# Holder_Accu_Simetric.net
KiCad netlist of a schematic drawn in Altium Designer
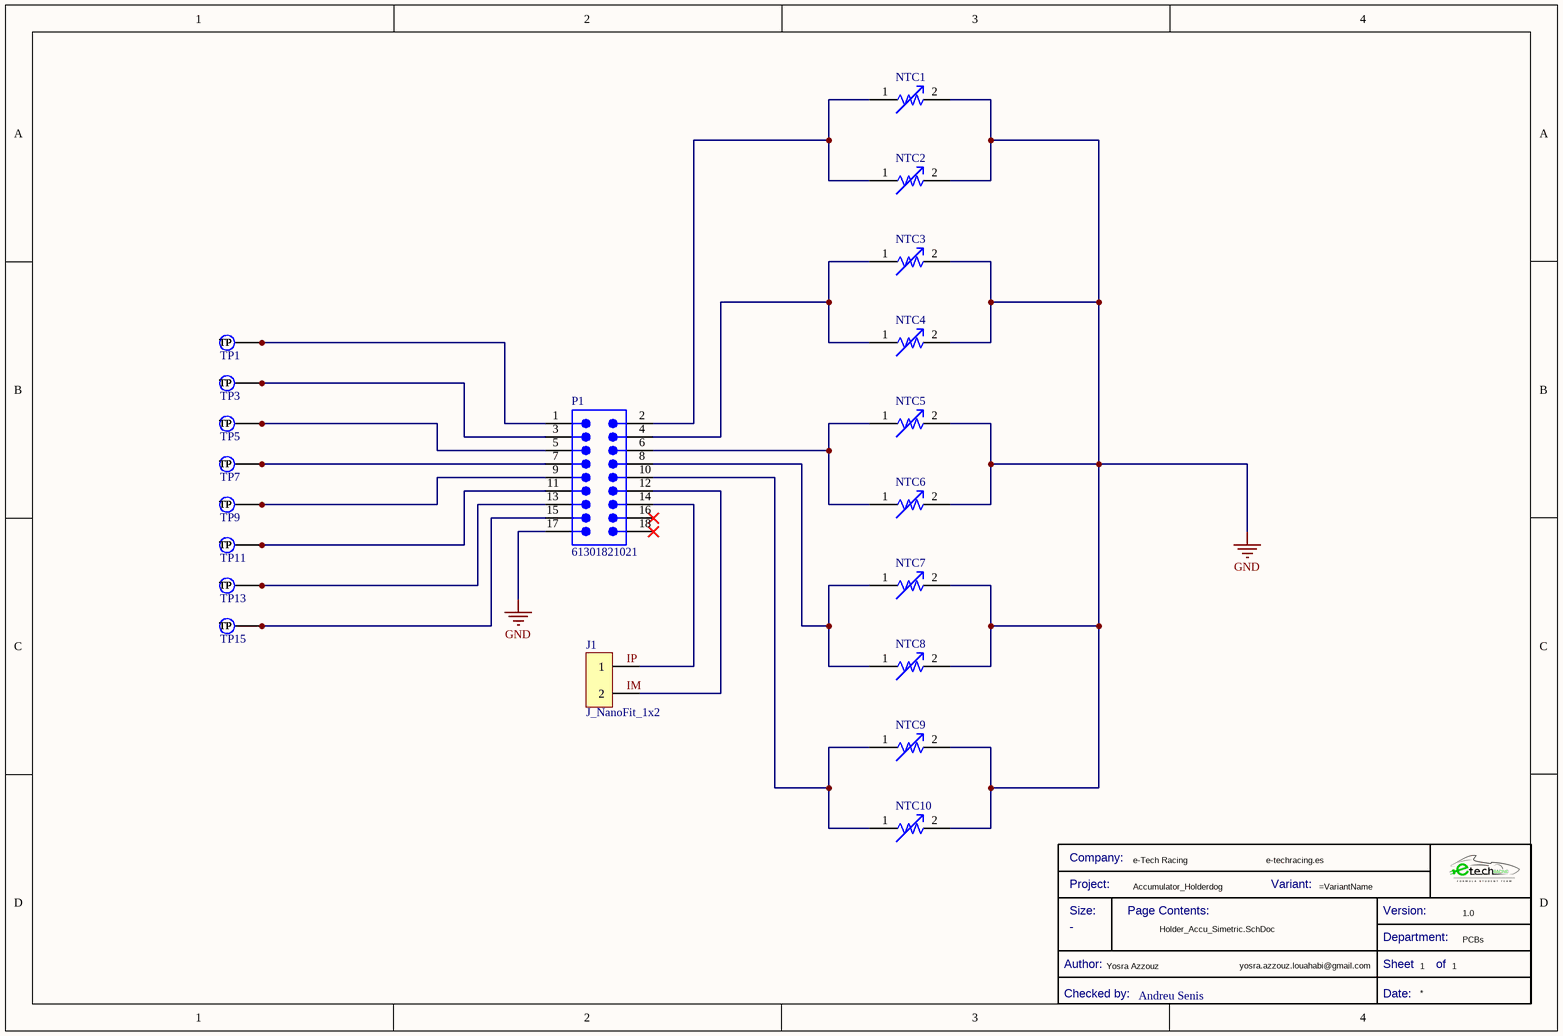
[diagram p0: Holder_Accu_Simetric.SchDoc]

(export (version "E")
  (design (tool "Eeschema 10.0.6"))
  (components
    (comp (ref "*")
      (value "Title Block_template")
      (description "Standard Title Block")
      (fields
        (field (name "SIZE") "-")
        (field (name ".CREATOR") "GP")
        (field (name ".PCBCHECK") "GP")
        (field (name ".SCHCHECK") "GP")
      )
      (libsource (lib "e-Tech_Racing") (part "Title Block_template"))
    )
    (comp (ref "J1")
      (value "J_NanoFit_1x2")
      (footprint "FP-105309-1102-MFG")
      (description "Conn HDR 2 POS 2.5mm Solder ST Thru-Hole 2 Terminal 1 Port Nano-Fit Tray")
      (libsource (lib "EMEA- E-Tech Racing- I'Escola d'Enginyeria de Barcelona Est") (part "Molex Nano-Fit"))
    )
    (comp (ref "NTC1")
      (value "NTC SMD 0805")
      (footprint "RESC2012X10N")
      (description "NTC 0805 package 10kR")
      (libsource (lib "EMEA- E-Tech Racing- I'Escola d'Enginyeria de Barcelona Est") (part "0805"))
    )
    (comp (ref "NTC2")
      (value "NTC SMD 0805")
      (footprint "RESC2012X10N")
      (description "NTC 0805 package 10kR")
      (libsource (lib "EMEA- E-Tech Racing- I'Escola d'Enginyeria de Barcelona Est") (part "0805"))
    )
    (comp (ref "NTC3")
      (value "NTC SMD 0805")
      (footprint "RESC2012X10N")
      (description "NTC 0805 package 10kR")
      (libsource (lib "EMEA- E-Tech Racing- I'Escola d'Enginyeria de Barcelona Est") (part "0805"))
    )
    (comp (ref "NTC4")
      (value "NTC SMD 0805")
      (footprint "RESC2012X10N")
      (description "NTC 0805 package 10kR")
      (libsource (lib "EMEA- E-Tech Racing- I'Escola d'Enginyeria de Barcelona Est") (part "0805"))
    )
    (comp (ref "NTC5")
      (value "NTC SMD 0805")
      (footprint "RESC2012X10N")
      (description "NTC 0805 package 10kR")
      (libsource (lib "EMEA- E-Tech Racing- I'Escola d'Enginyeria de Barcelona Est") (part "0805"))
    )
    (comp (ref "NTC6")
      (value "NTC SMD 0805")
      (footprint "RESC2012X10N")
      (description "NTC 0805 package 10kR")
      (libsource (lib "EMEA- E-Tech Racing- I'Escola d'Enginyeria de Barcelona Est") (part "0805"))
    )
    (comp (ref "NTC7")
      (value "NTC SMD 0805")
      (footprint "RESC2012X10N")
      (description "NTC 0805 package 10kR")
      (libsource (lib "EMEA- E-Tech Racing- I'Escola d'Enginyeria de Barcelona Est") (part "0805"))
    )
    (comp (ref "NTC8")
      (value "NTC SMD 0805")
      (footprint "RESC2012X10N")
      (description "NTC 0805 package 10kR")
      (libsource (lib "EMEA- E-Tech Racing- I'Escola d'Enginyeria de Barcelona Est") (part "0805"))
    )
    (comp (ref "NTC9")
      (value "NTC SMD 0805")
      (footprint "RESC2012X10N")
      (description "NTC 0805 package 10kR")
      (libsource (lib "EMEA- E-Tech Racing- I'Escola d'Enginyeria de Barcelona Est") (part "0805"))
    )
    (comp (ref "NTC10")
      (value "NTC SMD 0805")
      (footprint "RESC2012X10N")
      (description "NTC 0805 package 10kR")
      (libsource (lib "EMEA- E-Tech Racing- I'Escola d'Enginyeria de Barcelona Est") (part "0805"))
    )
    (comp (ref "P1")
      (value "61301821021")
      (footprint "61301821021")
      (libsource (lib "EMEA- E-Tech Racing- I'Escola d'Enginyeria de Barcelona Est") (part "Header_Male_2R_18P"))
    )
    (comp (ref "TP1")
      (value "Test Point")
      (footprint "TESTPOINT_WIDE")
      (description "TestPoint 5x5mm")
      (libsource (lib "e-Tech_Racing") (part "TestPoint_Wide"))
    )
    (comp (ref "TP3")
      (value "Test Point")
      (footprint "TESTPOINT_WIDE")
      (description "TestPoint 5x5mm")
      (libsource (lib "e-Tech_Racing") (part "TestPoint_Wide"))
    )
    (comp (ref "TP5")
      (value "Test Point")
      (footprint "TESTPOINT_WIDE")
      (description "TestPoint 5x5mm")
      (libsource (lib "e-Tech_Racing") (part "TestPoint_Wide"))
    )
    (comp (ref "TP7")
      (value "Test Point")
      (footprint "TESTPOINT_WIDE")
      (description "TestPoint 5x5mm")
      (libsource (lib "e-Tech_Racing") (part "TestPoint_Wide"))
    )
    (comp (ref "TP9")
      (value "Test Point")
      (footprint "TESTPOINT_WIDE")
      (description "TestPoint 5x5mm")
      (libsource (lib "e-Tech_Racing") (part "TestPoint_Wide"))
    )
    (comp (ref "TP11")
      (value "Test Point")
      (footprint "TESTPOINT_WIDE")
      (description "TestPoint 5x5mm")
      (libsource (lib "e-Tech_Racing") (part "TestPoint_Wide"))
    )
    (comp (ref "TP13")
      (value "Test Point")
      (footprint "TESTPOINT_WIDE")
      (description "TestPoint 5x5mm")
      (libsource (lib "e-Tech_Racing") (part "TestPoint_Wide"))
    )
    (comp (ref "TP15")
      (value "Test Point")
      (footprint "TESTPOINT_WIDE")
      (description "TestPoint 5x5mm")
      (libsource (lib "e-Tech_Racing") (part "TestPoint_Wide"))
    )
  )
  (nets
    (net (code "3") (name "GND") (class "Default")
      (node (ref "NTC1") (pin "2") (pinfunction "2_2") (pintype "passive"))
      (node (ref "NTC10") (pin "2") (pinfunction "2_2") (pintype "passive"))
      (node (ref "NTC2") (pin "2") (pinfunction "2_2") (pintype "passive"))
      (node (ref "NTC3") (pin "2") (pinfunction "2_2") (pintype "passive"))
      (node (ref "NTC4") (pin "2") (pinfunction "2_2") (pintype "passive"))
      (node (ref "NTC5") (pin "2") (pinfunction "2_2") (pintype "passive"))
      (node (ref "NTC6") (pin "2") (pinfunction "2_2") (pintype "passive"))
      (node (ref "NTC7") (pin "2") (pinfunction "2_2") (pintype "passive"))
      (node (ref "NTC8") (pin "2") (pinfunction "2_2") (pintype "passive"))
      (node (ref "NTC9") (pin "2") (pinfunction "2_2") (pintype "passive"))
      (node (ref "P1") (pin "17") (pinfunction "17_17") (pintype "passive"))
    )
    (net (code "4") (name "Net-(J1-Pad1)") (class "Default")
      (node (ref "J1") (pin "1") (pinfunction "1_1") (pintype "passive"))
      (node (ref "P1") (pin "14") (pinfunction "14_14") (pintype "passive"))
    )
    (net (code "5") (name "Net-(J1-Pad2)") (class "Default")
      (node (ref "J1") (pin "2") (pinfunction "2_2") (pintype "passive"))
      (node (ref "P1") (pin "12") (pinfunction "12_12") (pintype "passive"))
    )
    (net (code "6") (name "Net-(NTC1-Pad1)") (class "Default")
      (node (ref "NTC1") (pin "1") (pinfunction "1_1") (pintype "passive"))
      (node (ref "NTC2") (pin "1") (pinfunction "1_1") (pintype "passive"))
      (node (ref "P1") (pin "2") (pinfunction "2_2") (pintype "passive"))
    )
    (net (code "7") (name "Net-(NTC3-Pad1)") (class "Default")
      (node (ref "NTC3") (pin "1") (pinfunction "1_1") (pintype "passive"))
      (node (ref "NTC4") (pin "1") (pinfunction "1_1") (pintype "passive"))
      (node (ref "P1") (pin "4") (pinfunction "4_4") (pintype "passive"))
    )
    (net (code "8") (name "Net-(NTC5-Pad1)") (class "Default")
      (node (ref "NTC5") (pin "1") (pinfunction "1_1") (pintype "passive"))
      (node (ref "NTC6") (pin "1") (pinfunction "1_1") (pintype "passive"))
      (node (ref "P1") (pin "6") (pinfunction "6_6") (pintype "passive"))
    )
    (net (code "9") (name "Net-(NTC7-Pad1)") (class "Default")
      (node (ref "NTC7") (pin "1") (pinfunction "1_1") (pintype "passive"))
      (node (ref "NTC8") (pin "1") (pinfunction "1_1") (pintype "passive"))
      (node (ref "P1") (pin "8") (pinfunction "8_8") (pintype "passive"))
    )
    (net (code "10") (name "Net-(NTC10-Pad1)") (class "Default")
      (node (ref "NTC10") (pin "1") (pinfunction "1_1") (pintype "passive"))
      (node (ref "NTC9") (pin "1") (pinfunction "1_1") (pintype "passive"))
      (node (ref "P1") (pin "10") (pinfunction "10_10") (pintype "passive"))
    )
    (net (code "11") (name "Net-(TP1-TP)") (class "Default")
      (node (ref "P1") (pin "1") (pinfunction "1_1") (pintype "passive"))
      (node (ref "TP1") (pin "1") (pinfunction "TP_1") (pintype "passive"))
    )
    (net (code "12") (name "Net-(TP3-TP)") (class "Default")
      (node (ref "P1") (pin "3") (pinfunction "3_3") (pintype "passive"))
      (node (ref "TP3") (pin "1") (pinfunction "TP_1") (pintype "passive"))
    )
    (net (code "13") (name "Net-(TP5-TP)") (class "Default")
      (node (ref "P1") (pin "5") (pinfunction "5_5") (pintype "passive"))
      (node (ref "TP5") (pin "1") (pinfunction "TP_1") (pintype "passive"))
    )
    (net (code "14") (name "Net-(TP7-TP)") (class "Default")
      (node (ref "P1") (pin "7") (pinfunction "7_7") (pintype "passive"))
      (node (ref "TP7") (pin "1") (pinfunction "TP_1") (pintype "passive"))
    )
    (net (code "15") (name "Net-(TP9-TP)") (class "Default")
      (node (ref "P1") (pin "9") (pinfunction "9_9") (pintype "passive"))
      (node (ref "TP9") (pin "1") (pinfunction "TP_1") (pintype "passive"))
    )
    (net (code "16") (name "Net-(TP11-TP)") (class "Default")
      (node (ref "P1") (pin "11") (pinfunction "11_11") (pintype "passive"))
      (node (ref "TP11") (pin "1") (pinfunction "TP_1") (pintype "passive"))
    )
    (net (code "17") (name "Net-(TP13-TP)") (class "Default")
      (node (ref "P1") (pin "13") (pinfunction "13_13") (pintype "passive"))
      (node (ref "TP13") (pin "1") (pinfunction "TP_1") (pintype "passive"))
    )
    (net (code "18") (name "Net-(TP15-TP)") (class "Default")
      (node (ref "P1") (pin "15") (pinfunction "15_15") (pintype "passive"))
      (node (ref "TP15") (pin "1") (pinfunction "TP_1") (pintype "passive"))
    )
    (net (code "19") (name "unconnected-(P1-Pad16)") (class "Default")
      (node (ref "P1") (pin "16") (pinfunction "16_16") (pintype "passive+no_connect"))
    )
    (net (code "20") (name "unconnected-(P1-Pad18)") (class "Default")
      (node (ref "P1") (pin "18") (pinfunction "18_18") (pintype "passive+no_connect"))
    )
  )
)
